# Dogfish3D_-_Power.net
KiCad netlist of a schematic drawn in Altium Designer
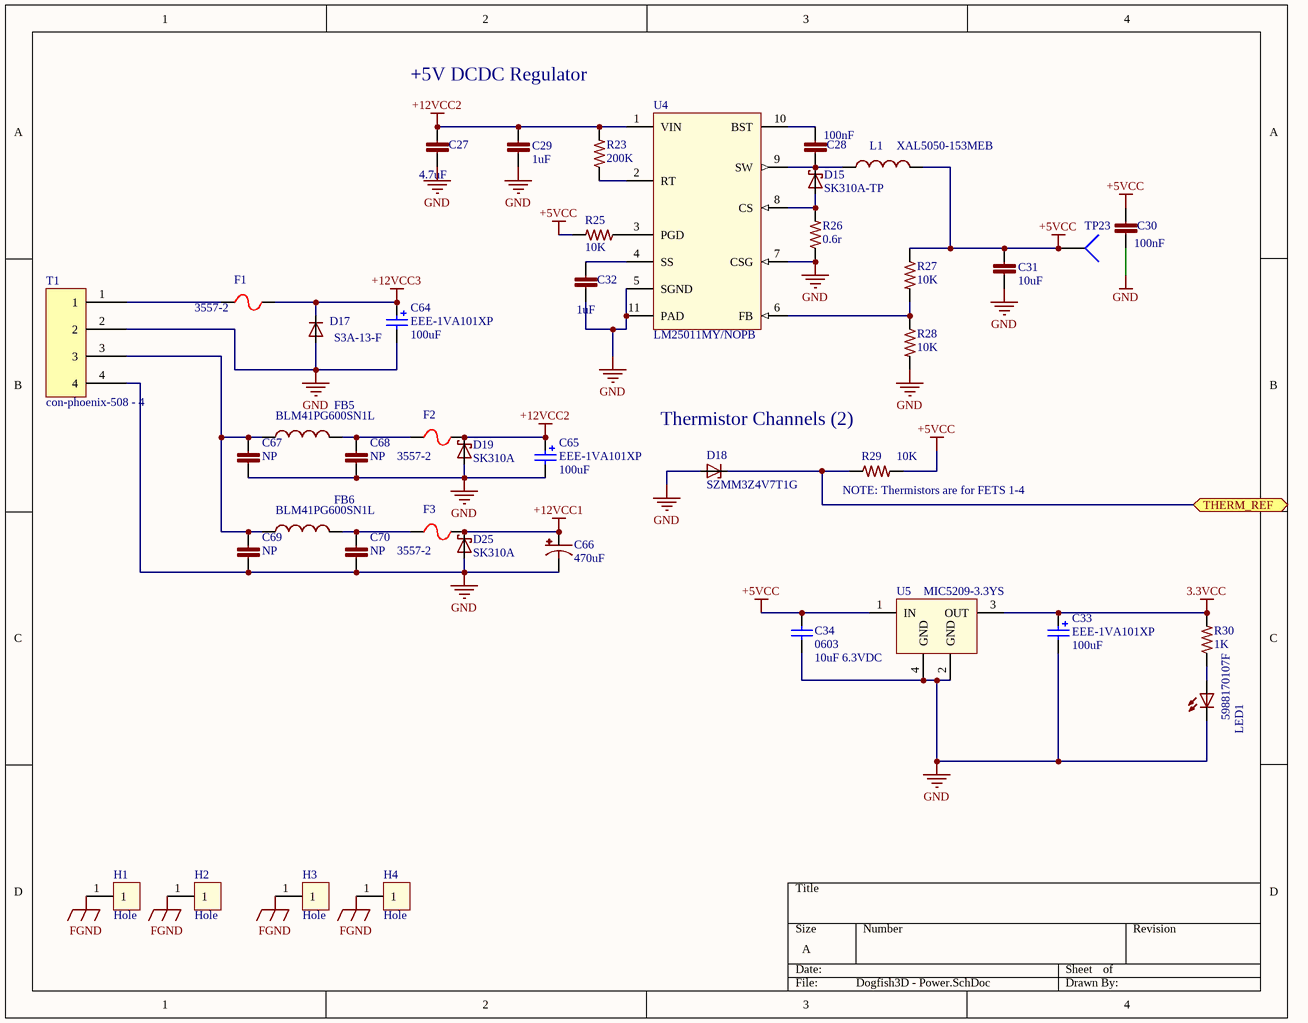
[diagram p0: Dogfish3D - Power.SchDoc]

(export (version "E")
  (design (tool "Eeschema 10.0.6"))
  (components
    (comp (ref "C27")
      (value "4.7uF")
      (footprint "C1206")
      (description "CAP CER 1206 4.7uF 50V 10% X5R")
      (fields
        (field (name "MANUFACTURERPARTNUMBER") "C1206C475K5PACTU")
        (field (name "PUBLISHER") "UltiMachine")
      )
      (libsource (lib "3Delight") (part "C1206C475K5PACTU"))
    )
    (comp (ref "C28")
      (value "100nF")
      (footprint "C0603")
      (description "CAP CER 0603 100nF 50V 10% X7R")
      (fields
        (field (name "MANUFACTURERPARTNUMBER") "C0603C104K5RACTU")
        (field (name "PUBLISHER") "UltiMachine")
      )
      (libsource (lib "3Delight") (part "C0603C104K5RACTU"))
    )
    (comp (ref "C29")
      (value "1uF")
      (footprint "C0805")
      (description "CAP CER 0805 1uF 50V 10% X7R")
      (fields
        (field (name "MANUFACTURERPARTNUMBER") "GRM21BR71H105KA12L")
        (field (name "PUBLISHER") "UltiMachine")
      )
      (libsource (lib "3Delight") (part "GRM21BR71H105KA12L"))
    )
    (comp (ref "C30")
      (value "100nF")
      (footprint "C0603")
      (description "CAP CER 0603 100nF 50V 10% X7R")
      (fields
        (field (name "MANUFACTURERPARTNUMBER") "C0603C104K5RACTU")
        (field (name "PUBLISHER") "UltiMachine")
      )
      (libsource (lib "3Delight") (part "C0603C104K5RACTU"))
    )
    (comp (ref "C31")
      (value "10uF")
      (footprint "C0805")
      (description "CAP CER 0805 10uF 10V 10% X5R")
      (fields
        (field (name "MANUFACTURERPARTNUMBER") "C0805C106K8PACTU")
        (field (name "PUBLISHER") "UltiMachine")
      )
      (libsource (lib "3Delight") (part "C0805C106K8PACTU"))
    )
    (comp (ref "C32")
      (value "1uF")
      (footprint "C0402")
      (description "CAP CER 0402 1uF 6.3V 10% X5R")
      (fields
        (field (name "MANUFACTURERPARTNUMBER") "GRM155R60J105KE19D")
        (field (name "PUBLISHER") "UltiMachine")
      )
      (libsource (lib "3Delight") (part "GRM155R60J105KE19D"))
    )
    (comp (ref "C33")
      (value "EEE-1VA101XP")
      (footprint "EEE-1VA101XP")
      (description "CAP ALUM 100UF 35V 20% SMD")
      (fields (field (name "DIGIKEY PART #") "PCE3951CT-ND") (field (name "ALTIUM_VALUE") "100uF"))
      (libsource (lib "Tigershark3D") (part "EEE-1VA101XP"))
    )
    (comp (ref "C34")
      (value "0603")
      (footprint "C0603")
      (description "CAP CER 10UF 6.3V 10% JB 0603")
      (fields
        (field (name "MFR PART #") "C1608JB0J106K080AB")
        (field (name "MFR") "TDK")
        (field (name "ALTIUM_VALUE") "10uF 6.3VDC")
      )
      (libsource (lib "Tigershark3D") (part "C1608JB0J106K080AB"))
    )
    (comp (ref "C64")
      (value "EEE-1VA101XP")
      (footprint "EEE-1VA101XP")
      (description "CAP ALUM 100UF 35V 20% SMD")
      (fields (field (name "DIGIKEY PART #") "PCE3951CT-ND") (field (name "ALTIUM_VALUE") "100uF"))
      (libsource (lib "Tigershark3D") (part "EEE-1VA101XP"))
    )
    (comp (ref "C65")
      (value "EEE-1VA101XP")
      (footprint "EEE-1VA101XP")
      (description "CAP ALUM 100UF 35V 20% SMD")
      (fields (field (name "DIGIKEY PART #") "PCE3951CT-ND") (field (name "ALTIUM_VALUE") "100uF"))
      (libsource (lib "Tigershark3D") (part "EEE-1VA101XP"))
    )
    (comp (ref "C66")
      (value "470uF")
      (footprint "C12,5-5")
      (description "CAP ALU 470uF 50V 20%")
      (fields
        (field (name "MANUFACTURERPARTNUMBER") "UPW1H471MHD1TO")
        (field (name "PUBLISHER") "UltiMachine")
      )
      (libsource (lib "Tigershark3D") (part "UPW1H471MHD1TO"))
    )
    (comp (ref "C67")
      (value "NP")
      (footprint "C0603")
      (description "CAP CER 0603 100nF 50V 10% X7R")
      (fields
        (field (name "MANUFACTURERPARTNUMBER") "C0603C104K5RACTU")
        (field (name "PUBLISHER") "UltiMachine")
      )
      (libsource (lib "3Delight") (part "C0603C104K5RACTU"))
    )
    (comp (ref "C68")
      (value "NP")
      (footprint "C0603")
      (description "CAP CER 0603 100nF 50V 10% X7R")
      (fields
        (field (name "MANUFACTURERPARTNUMBER") "C0603C104K5RACTU")
        (field (name "PUBLISHER") "UltiMachine")
      )
      (libsource (lib "3Delight") (part "C0603C104K5RACTU"))
    )
    (comp (ref "C69")
      (value "NP")
      (footprint "C0603")
      (description "CAP CER 0603 100nF 50V 10% X7R")
      (fields
        (field (name "MANUFACTURERPARTNUMBER") "C0603C104K5RACTU")
        (field (name "PUBLISHER") "UltiMachine")
      )
      (libsource (lib "3Delight") (part "C0603C104K5RACTU"))
    )
    (comp (ref "C70")
      (value "NP")
      (footprint "C0603")
      (description "CAP CER 0603 100nF 50V 10% X7R")
      (fields
        (field (name "MANUFACTURERPARTNUMBER") "C0603C104K5RACTU")
        (field (name "PUBLISHER") "UltiMachine")
      )
      (libsource (lib "3Delight") (part "C0603C104K5RACTU"))
    )
    (comp (ref "D15")
      (value "SK310A-TP")
      (footprint "SMA-SM")
      (description "DIODE Schottky 3A SMA")
      (fields (field (name "MANUFACTURERPARTNUMBER") "SK310A") (field (name "PUBLISHER") "UltiMachine"))
      (libsource (lib "3Delight") (part "SK310A"))
    )
    (comp (ref "D17")
      (value "S3A-13-F")
      (footprint "DO-214AB")
      (description "DIODE DO-214AB")
      (fields (field (name "PUBLISHER") "UltiMachine"))
      (libsource (lib "3Delight") (part "S3A-13-F"))
    )
    (comp (ref "D18")
      (value "SZMM3Z4V7T1G")
      (footprint "SOD323-R")
      (description "Z-Diode")
      (fields (field (name "MANUFACTURER") "Fairchild") (field (name "PUBLISHER") "UltiMachine"))
      (libsource (lib "Tigershark3D") (part "SZMM3Z4V7T1G"))
    )
    (comp (ref "D19")
      (value "SK310A")
      (footprint "SMA-SM")
      (description "DIODE Schottky 3A SMA")
      (fields (field (name "PUBLISHER") "UltiMachine"))
      (libsource (lib "3Delight") (part "SK310A"))
    )
    (comp (ref "D25")
      (value "SK310A")
      (footprint "SMA-SM")
      (description "DIODE Schottky 3A SMA")
      (fields (field (name "PUBLISHER") "UltiMachine"))
      (libsource (lib "3Delight") (part "SK310A"))
    )
    (comp (ref "F1")
      (value "3557-2")
      (footprint "3557")
      (description "FUSE PTH ATO")
      (fields (field (name "PUBLISHER") "UltiMachine"))
      (libsource (lib "3Delight") (part "3557-2"))
    )
    (comp (ref "F2")
      (value "3557-2")
      (footprint "3557")
      (description "FUSE PTH ATO")
      (fields (field (name "PUBLISHER") "UltiMachine"))
      (libsource (lib "3Delight") (part "3557-2"))
    )
    (comp (ref "F3")
      (value "3557-2")
      (footprint "3557")
      (description "FUSE PTH ATO")
      (fields (field (name "PUBLISHER") "UltiMachine"))
      (libsource (lib "3Delight") (part "3557-2"))
    )
    (comp (ref "FB5")
      (value "BLM41PG600SN1L")
      (footprint "L1806")
      (description "FERRITE BEAD 1806 60ohm")
      (fields (field (name "PUBLISHER") "UltiMachine"))
      (libsource (lib "3Delight") (part "BLM41PG600SN1L"))
    )
    (comp (ref "FB6")
      (value "BLM41PG600SN1L")
      (footprint "L1806")
      (description "FERRITE BEAD 1806 60ohm")
      (fields (field (name "PUBLISHER") "UltiMachine"))
      (libsource (lib "3Delight") (part "BLM41PG600SN1L"))
    )
    (comp (ref "H1")
      (value "Hole")
      (footprint "Wave_hole_3x7-singleSided")
      (libsource (lib "3Delight") (part "Hole"))
    )
    (comp (ref "H2")
      (value "Hole")
      (footprint "Wave_hole_3x7-singleSided")
      (libsource (lib "3Delight") (part "Hole"))
    )
    (comp (ref "H3")
      (value "Hole")
      (footprint "Wave_hole_3x7-singleSided")
      (libsource (lib "3Delight") (part "Hole"))
    )
    (comp (ref "H4")
      (value "Hole")
      (footprint "Wave_hole_3x7-singleSided")
      (libsource (lib "3Delight") (part "Hole"))
    )
    (comp (ref "L1")
      (value "XAL5050-153MEB")
      (footprint "XAL50xx-153")
      (description "IND 15uH 3.9A 20%")
      (fields (field (name "PUBLISHER") "UltiMachine"))
      (libsource (lib "3Delight") (part "XAL5050-153MEB"))
    )
    (comp (ref "LED1")
      (value "5988170107F")
      (footprint "LED2012120")
      (description "LED 0805 Green")
      (fields (field (name "PUBLISHER") "UltiMachine"))
      (libsource (lib "3Delight") (part "5988170107F"))
    )
    (comp (ref "R23")
      (value "200K")
      (footprint "R0402")
      (description "RES 0402 22r 63mW 1%")
      (fields
        (field (name "MANUFACTURERPARTNUMBER") "CRCW0402200KFKED")
        (field (name "PUBLISHER") "UltiMachine")
      )
      (libsource (lib "3Delight") (part "CRCW0402200KFKED"))
    )
    (comp (ref "R25")
      (value "10K")
      (footprint "R0603")
      (description "RES 0603 10K 100mW 1%")
      (fields
        (field (name "MANUFACTURERPARTNUMBER") "ERJ-3EKF1002V")
        (field (name "PUBLISHER") "UltiMachine")
      )
      (libsource (lib "3Delight") (part "ERJ-3EKF1002V"))
    )
    (comp (ref "R26")
      (value "0.6r")
      (footprint "2512R-0.55")
      (description "RES 0.06 OHM 1W 1% 2512 SMD")
      (fields
        (field (name "MANUFACTURERPARTNUMBER") "RL2512FK-070R06L")
        (field (name "PUBLISHER") "UltiMachine")
      )
      (libsource (lib "3Delight") (part "RL2512FK-070R06L"))
    )
    (comp (ref "R27")
      (value "10K")
      (footprint "R0603")
      (description "RES 0603 10K 100mW 1%")
      (fields
        (field (name "MANUFACTURERPARTNUMBER") "ERJ-3EKF1002V")
        (field (name "PUBLISHER") "UltiMachine")
      )
      (libsource (lib "3Delight") (part "ERJ-3EKF1002V"))
    )
    (comp (ref "R28")
      (value "10K")
      (footprint "R0603")
      (description "RES 0603 10K 100mW 1%")
      (fields
        (field (name "MANUFACTURERPARTNUMBER") "ERJ-3EKF1002V")
        (field (name "PUBLISHER") "UltiMachine")
      )
      (libsource (lib "3Delight") (part "ERJ-3EKF1002V"))
    )
    (comp (ref "R29")
      (value "10K")
      (footprint "R0603")
      (description "RES 0603 10K 100mW 1%")
      (fields
        (field (name "MANUFACTURERPARTNUMBER") "ERJ-3EKF1002V")
        (field (name "PUBLISHER") "UltiMachine")
      )
      (libsource (lib "3Delight") (part "ERJ-3EKF1002V"))
    )
    (comp (ref "R30")
      (value "1K")
      (footprint "R0603")
      (description "RES 0603 1K 100mW 1%")
      (fields
        (field (name "MANUFACTURERPARTNUMBER") "ERJ-3EKF1001V")
        (field (name "PUBLISHER") "UltiMachine")
      )
      (libsource (lib "Tigershark3D") (part "ERJ-3EKF1001V"))
    )
    (comp (ref "T1")
      (value "con-phoenix-508 - 4")
      (footprint "MSTBV4")
      (libsource (lib "ZMBo Schematic Library") (part "con-phoenix-508_4"))
    )
    (comp (ref "TP23")
      (value "TP4")
      (footprint "TP-2")
      (description "Socket")
      (fields (field (name "PUBLISHER") "Altium Limited"))
      (libsource (lib "ZMBo Schematic Library") (part "Socket"))
    )
    (comp (ref "U4")
      (value "LM25011MY/NOPB")
      (footprint "VSSOP10")
      (description "REG BUCK")
      (libsource (lib "3Delight") (part "LM25011"))
    )
    (comp (ref "U5")
      (value "MIC5209-3.3YS")
      (footprint "SOT230P700X190-4N")
      (libsource (lib "3Delight") (part "MIC5209-3.3YS"))
    )
  )
  (nets
    (net (code "1") (name "+5VCC") (class "Default")
      (node (ref "C30") (pin "1") (pinfunction "1_1") (pintype "passive"))
      (node (ref "C31") (pin "1") (pinfunction "1_1") (pintype "passive"))
      (node (ref "C34") (pin "2") (pinfunction "2_2") (pintype "passive"))
      (node (ref "L1") (pin "2") (pinfunction "2_2") (pintype "passive"))
      (node (ref "R25") (pin "2") (pinfunction "2_2") (pintype "passive"))
      (node (ref "R27") (pin "1") (pinfunction "1_1") (pintype "passive"))
      (node (ref "R29") (pin "2") (pinfunction "2_2") (pintype "passive"))
      (node (ref "TP23") (pin "1") (pinfunction "1_1") (pintype "passive"))
      (node (ref "U5") (pin "1") (pinfunction "IN_1") (pintype "power_in"))
    )
    (net (code "2") (name "+12VCC1") (class "Default")
      (node (ref "C66") (pin "1") (pinfunction "+_1") (pintype "passive"))
      (node (ref "D25") (pin "C") (pinfunction "C_C") (pintype "passive"))
      (node (ref "F3") (pin "2") (pinfunction "2_2") (pintype "passive"))
    )
    (net (code "3") (name "+12VCC2") (class "Default")
      (node (ref "C27") (pin "1") (pinfunction "1_1") (pintype "passive"))
      (node (ref "C29") (pin "1") (pinfunction "1_1") (pintype "passive"))
      (node (ref "C65") (pin "1") (pinfunction "1_1") (pintype "passive"))
      (node (ref "D19") (pin "C") (pinfunction "C_C") (pintype "passive"))
      (node (ref "F2") (pin "2") (pinfunction "2_2") (pintype "passive"))
      (node (ref "R23") (pin "2") (pinfunction "2_2") (pintype "passive"))
      (node (ref "U4") (pin "1") (pinfunction "VIN_1") (pintype "power_in"))
    )
    (net (code "4") (name "+12VCC3") (class "Default")
      (node (ref "C64") (pin "1") (pinfunction "1_1") (pintype "passive"))
      (node (ref "D17") (pin "C") (pinfunction "C_C") (pintype "passive"))
      (node (ref "F1") (pin "2") (pinfunction "2_2") (pintype "passive"))
    )
    (net (code "5") (name "/THERM_REF") (class "Default")
      (node (ref "D18") (pin "C") (pinfunction "C_C") (pintype "passive"))
      (node (ref "R29") (pin "1") (pinfunction "1_1") (pintype "passive"))
    )
    (net (code "6") (name "3.3VCC") (class "Default")
      (node (ref "C33") (pin "1") (pinfunction "1_1") (pintype "passive"))
      (node (ref "R30") (pin "2") (pinfunction "2_2") (pintype "passive"))
      (node (ref "U5") (pin "3") (pinfunction "OUT_3") (pintype "power_in"))
    )
    (net (code "7") (name "FGND") (class "Default")
      (node (ref "H1") (pin "1") (pinfunction "1_1") (pintype "power_in"))
      (node (ref "H2") (pin "1") (pinfunction "1_1") (pintype "power_in"))
      (node (ref "H3") (pin "1") (pinfunction "1_1") (pintype "power_in"))
      (node (ref "H4") (pin "1") (pinfunction "1_1") (pintype "power_in"))
    )
    (net (code "8") (name "GND") (class "Default")
      (node (ref "C27") (pin "2") (pinfunction "2_2") (pintype "passive"))
      (node (ref "C29") (pin "2") (pinfunction "2_2") (pintype "passive"))
      (node (ref "C30") (pin "2") (pinfunction "2_2") (pintype "passive"))
      (node (ref "C31") (pin "2") (pinfunction "2_2") (pintype "passive"))
      (node (ref "C32") (pin "2") (pinfunction "2_2") (pintype "passive"))
      (node (ref "C33") (pin "2") (pinfunction "2_2") (pintype "passive"))
      (node (ref "C34") (pin "1") (pinfunction "1_1") (pintype "passive"))
      (node (ref "C64") (pin "2") (pinfunction "2_2") (pintype "passive"))
      (node (ref "C65") (pin "2") (pinfunction "2_2") (pintype "passive"))
      (node (ref "C66") (pin "2") (pinfunction "-_2") (pintype "passive"))
      (node (ref "C67") (pin "2") (pinfunction "2_2") (pintype "passive"))
      (node (ref "C68") (pin "2") (pinfunction "2_2") (pintype "passive"))
      (node (ref "C69") (pin "2") (pinfunction "2_2") (pintype "passive"))
      (node (ref "C70") (pin "2") (pinfunction "2_2") (pintype "passive"))
      (node (ref "D17") (pin "A") (pinfunction "A_A") (pintype "passive"))
      (node (ref "D18") (pin "A") (pinfunction "A_A") (pintype "passive"))
      (node (ref "D19") (pin "A") (pinfunction "A_A") (pintype "passive"))
      (node (ref "D25") (pin "A") (pinfunction "A_A") (pintype "passive"))
      (node (ref "LED1") (pin "C") (pinfunction "C_C") (pintype "passive"))
      (node (ref "R26") (pin "1") (pinfunction "1_1") (pintype "passive"))
      (node (ref "R28") (pin "2") (pinfunction "2_2") (pintype "passive"))
      (node (ref "T1") (pin "2") (pinfunction "2_2") (pintype "passive"))
      (node (ref "T1") (pin "4") (pinfunction "4_4") (pintype "passive"))
      (node (ref "U4") (pin "11") (pinfunction "PAD_11") (pintype "power_in"))
      (node (ref "U4") (pin "5") (pinfunction "SGND_5") (pintype "power_in"))
      (node (ref "U4") (pin "7") (pinfunction "CSG_7") (pintype "input"))
      (node (ref "U5") (pin "2") (pinfunction "GND_2") (pintype "power_in"))
      (node (ref "U5") (pin "4") (pinfunction "GND_4") (pintype "power_in"))
    )
    (net (code "9") (name "Net-(C67-Pad1)") (class "Default")
      (node (ref "C67") (pin "1") (pinfunction "1_1") (pintype "passive"))
      (node (ref "C69") (pin "1") (pinfunction "1_1") (pintype "passive"))
      (node (ref "FB5") (pin "1") (pinfunction "1_1") (pintype "passive"))
      (node (ref "FB6") (pin "1") (pinfunction "1_1") (pintype "passive"))
      (node (ref "T1") (pin "3") (pinfunction "3_3") (pintype "passive"))
    )
    (net (code "10") (name "Net-(C68-Pad1)") (class "Default")
      (node (ref "C68") (pin "1") (pinfunction "1_1") (pintype "passive"))
      (node (ref "F2") (pin "1") (pinfunction "1_1") (pintype "passive"))
      (node (ref "FB5") (pin "2") (pinfunction "2_2") (pintype "passive"))
    )
    (net (code "11") (name "Net-(C70-Pad1)") (class "Default")
      (node (ref "C70") (pin "1") (pinfunction "1_1") (pintype "passive"))
      (node (ref "F3") (pin "1") (pinfunction "1_1") (pintype "passive"))
      (node (ref "FB6") (pin "2") (pinfunction "2_2") (pintype "passive"))
    )
    (net (code "12") (name "Net-(F1-Pad1)") (class "Default")
      (node (ref "F1") (pin "1") (pinfunction "1_1") (pintype "passive"))
      (node (ref "T1") (pin "1") (pinfunction "1_1") (pintype "passive"))
    )
    (net (code "13") (name "Net-(LED1-PadA)") (class "Default")
      (node (ref "LED1") (pin "A") (pinfunction "A_A") (pintype "passive"))
      (node (ref "R30") (pin "1") (pinfunction "1_1") (pintype "passive"))
    )
    (net (code "14") (name "Net-(U4-BST)") (class "Default")
      (node (ref "C28") (pin "1") (pinfunction "1_1") (pintype "passive"))
      (node (ref "U4") (pin "10") (pinfunction "BST_10") (pintype "power_in"))
    )
    (net (code "15") (name "Net-(U4-CS)") (class "Default")
      (node (ref "D15") (pin "A") (pinfunction "A_A") (pintype "passive"))
      (node (ref "R26") (pin "2") (pinfunction "2_2") (pintype "passive"))
      (node (ref "U4") (pin "8") (pinfunction "CS_8") (pintype "input"))
    )
    (net (code "16") (name "Net-(U4-FB)") (class "Default")
      (node (ref "R27") (pin "2") (pinfunction "2_2") (pintype "passive"))
      (node (ref "R28") (pin "1") (pinfunction "1_1") (pintype "passive"))
      (node (ref "U4") (pin "6") (pinfunction "FB_6") (pintype "input"))
    )
    (net (code "17") (name "Net-(U4-PGD)") (class "Default")
      (node (ref "R25") (pin "1") (pinfunction "1_1") (pintype "passive"))
      (node (ref "U4") (pin "3") (pinfunction "PGD_3") (pintype "power_in"))
    )
    (net (code "18") (name "Net-(U4-RT)") (class "Default")
      (node (ref "R23") (pin "1") (pinfunction "1_1") (pintype "passive"))
      (node (ref "U4") (pin "2") (pinfunction "RT_2") (pintype "power_in"))
    )
    (net (code "19") (name "Net-(U4-SS)") (class "Default")
      (node (ref "C32") (pin "1") (pinfunction "1_1") (pintype "passive"))
      (node (ref "U4") (pin "4") (pinfunction "SS_4") (pintype "power_in"))
    )
    (net (code "20") (name "Net-(U4-SW)") (class "Default")
      (node (ref "C28") (pin "2") (pinfunction "2_2") (pintype "passive"))
      (node (ref "D15") (pin "C") (pinfunction "C_C") (pintype "passive"))
      (node (ref "L1") (pin "1") (pinfunction "1_1") (pintype "passive"))
      (node (ref "U4") (pin "9") (pinfunction "SW_9") (pintype "output"))
    )
  )
)
